# Power_and_CAN_Bus.net
KiCad netlist of a schematic drawn in Altium Designer
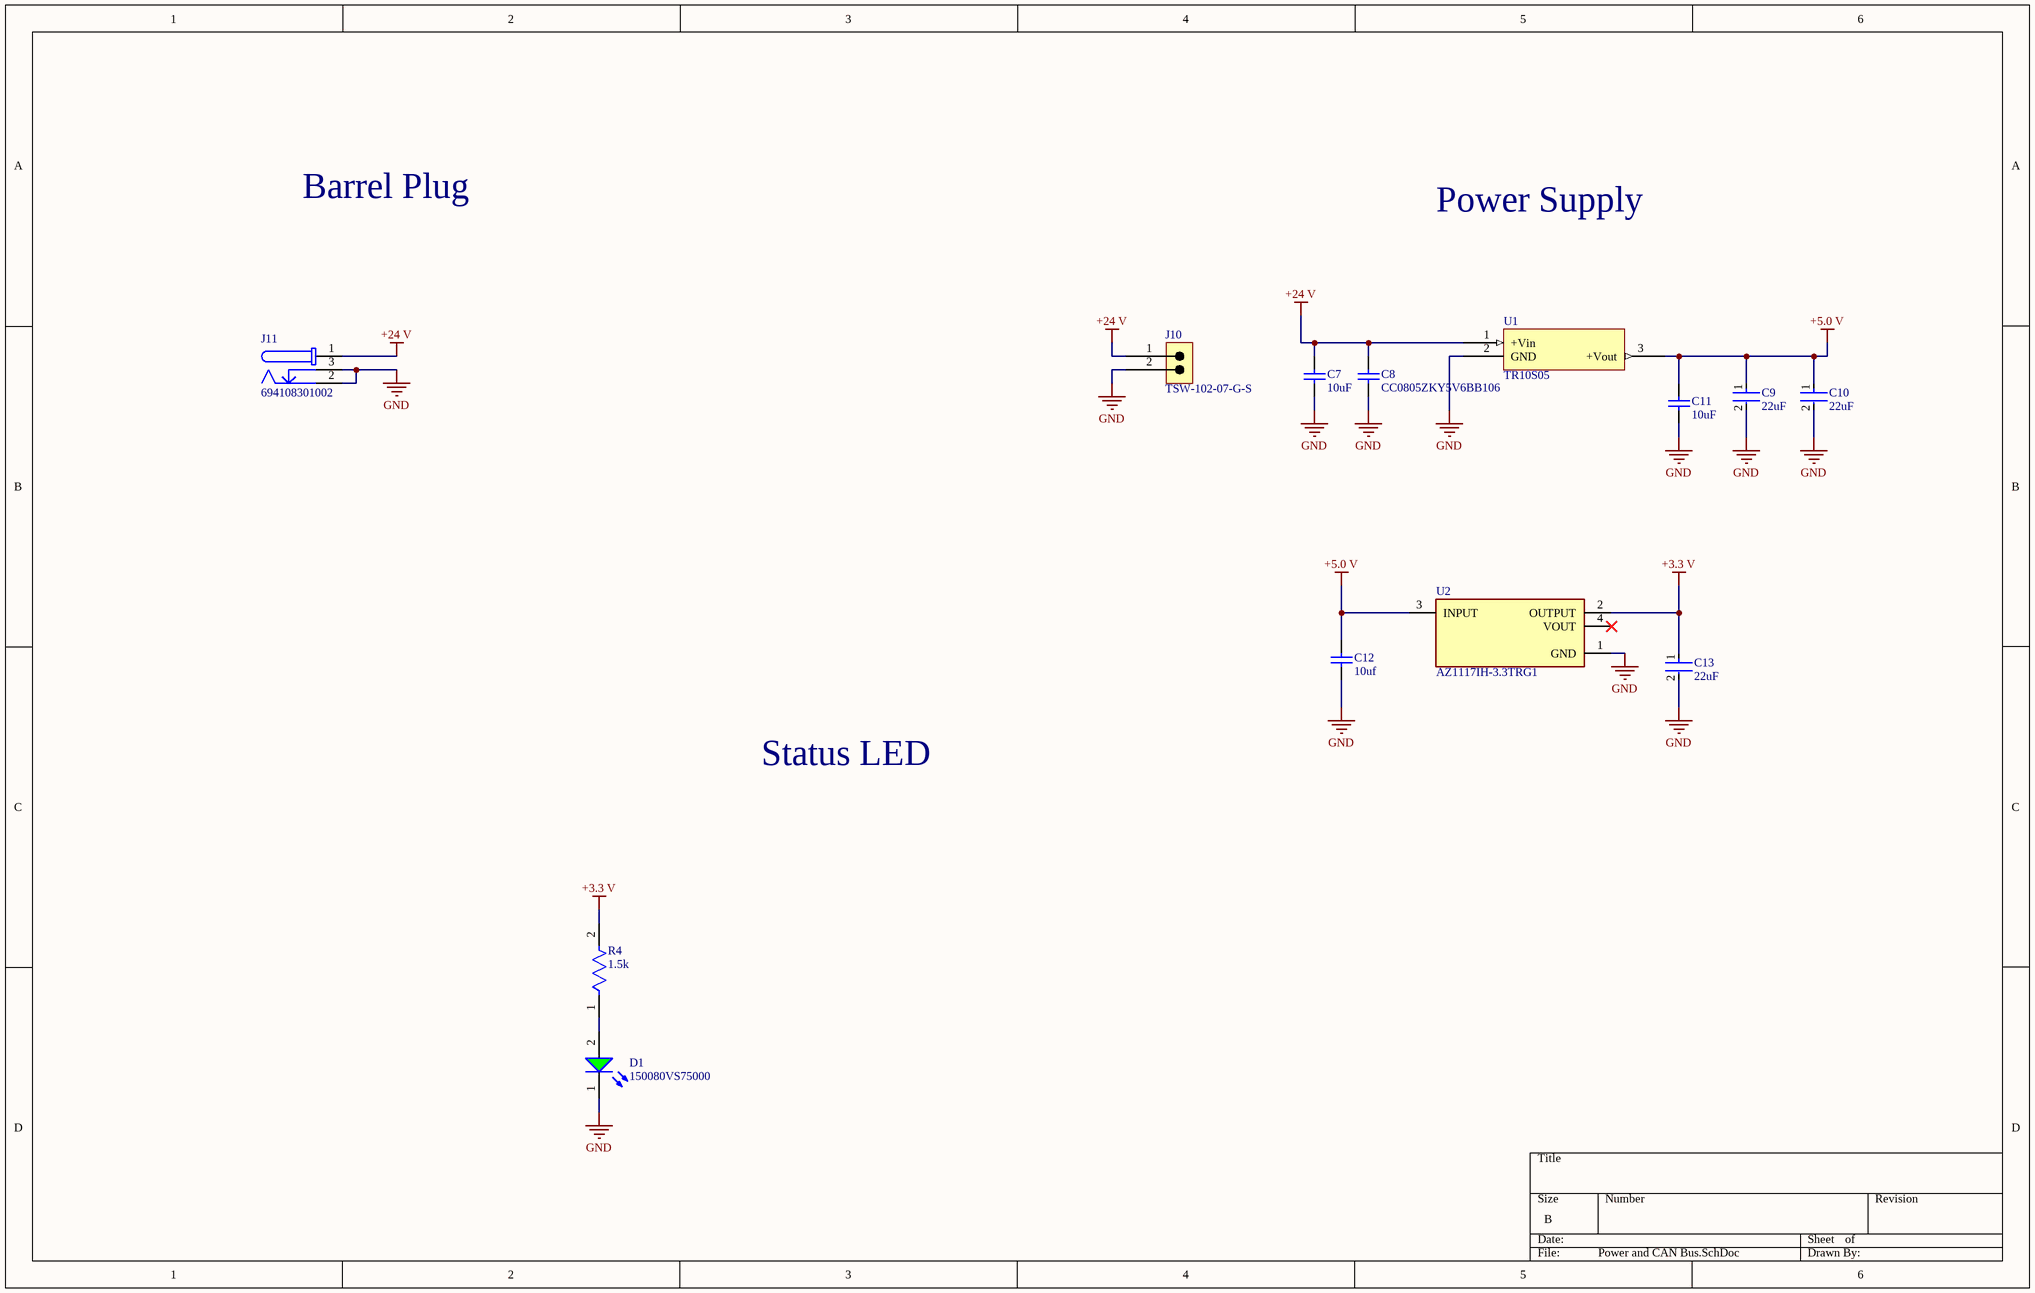
[diagram p0: Power and CAN Bus.SchDoc]

(export (version "E")
  (design (tool "Eeschema 10.0.6"))
  (components
    (comp (ref "C7")
      (value "10uF")
      (footprint "CC0805ZKY5V6BB106-Footprint-1")
      (libsource (lib "C0514760 C0514760") (part "CAP-NP-2"))
    )
    (comp (ref "C8")
      (value "CC0805ZKY5V6BB106")
      (footprint "CC0805ZKY5V6BB106-Footprint-1")
      (libsource (lib "C0514760 C0514760") (part "CAP-NP-2"))
    )
    (comp (ref "C9")
      (value "22uF")
      (footprint "FP-GMC21R-IPC_B")
      (libsource (lib "C0514760 C0514760") (part "b4654b650e69147ec39a6b967a45e02"))
    )
    (comp (ref "C10")
      (value "22uF")
      (footprint "FP-GMC21R-IPC_B")
      (libsource (lib "C0514760 C0514760") (part "b4654b650e69147ec39a6b967a45e02"))
    )
    (comp (ref "C11")
      (value "10uF")
      (footprint "CC0805ZKY5V6BB106-Footprint-1")
      (libsource (lib "C0514760 C0514760") (part "CAP-NP-2"))
    )
    (comp (ref "C12")
      (value "10uf")
      (footprint "CC0805ZKY5V6BB106-Footprint-1")
      (libsource (lib "C0514760 C0514760") (part "CAP-NP-2"))
    )
    (comp (ref "C13")
      (value "22uF")
      (footprint "FP-GMC21R-IPC_B")
      (libsource (lib "C0514760 C0514760") (part "b4654b650e69147ec39a6b967a45e02"))
    )
    (comp (ref "D1")
      (value "150080VS75000")
      (footprint "WL-SMCW_0805_150080xx75000")
      (description "Single Color LED, Bright Green, Water Clear, 1.4mm")
      (libsource (lib "C0514760 C0514760") (part "LED_Green_2A-1K"))
    )
    (comp (ref "J10")
      (value "TSW-102-07-G-S")
      (footprint "FP-TSW-102-07-G-S-MFG")
      (libsource (lib "C0514760 C0514760") (part "3bc925449376181038e59eaffc5286c"))
    )
    (comp (ref "J11")
      (value "694108301002")
      (footprint "694108301002")
      (description "DC Power Jack Connector WR-DC, Male, Right Angled, THT, 5 A, 24 V")
      (libsource (lib "C0514760 C0514760") (part "DC Power Jack"))
    )
    (comp (ref "R4")
      (value "1.5k")
      (footprint "FP-RT0805-IPC_A")
      (description "Fixed Resistor, Thin Film, 0.125W, 1500ohm, 150V, 1% +/-Tol, 50ppm/Cel, Surface Mount, 0805")
      (fields (field (name "POWER") "125mW") (field (name "TOLERANCE") "1%"))
      (libsource (lib "C0514760 C0514760") (part "1029c3af85768c4190bb7ad29bc67b5"))
    )
    (comp (ref "U1")
      (value "TR10S05")
      (footprint "TR10S05-Footprint-1")
      (description "DC-DC Regulated Power Supply Module")
      (libsource (lib "C0514760 C0514760") (part "TR10S05-Symbol-1"))
    )
    (comp (ref "U2")
      (value "AZ1117IH-3.3TRG1")
      (footprint "FP-SOT223-IPC_B")
      (description "Fixed Positive LDO Regulator, 3.3V, 1.3V Dropout, PDSO3")
      (libsource (lib "C0514760 C0514760") (part "3c8a0cc3f7d1fafcf032f21e1bb5f65"))
    )
  )
  (nets
    (net (code "1") (name "+3.3 V") (class "Default")
      (node (ref "C13") (pin "1") (pinfunction "1_1") (pintype "passive"))
      (node (ref "R4") (pin "2") (pinfunction "2_2") (pintype "passive"))
      (node (ref "U2") (pin "2") (pinfunction "OUTPUT_2") (pintype "power_in"))
    )
    (net (code "2") (name "+5.0 V") (class "Default")
      (node (ref "C10") (pin "1") (pinfunction "1_1") (pintype "passive"))
      (node (ref "C11") (pin "2") (pinfunction "2_2") (pintype "passive"))
      (node (ref "C12") (pin "2") (pinfunction "2_2") (pintype "passive"))
      (node (ref "C9") (pin "1") (pinfunction "1_1") (pintype "passive"))
      (node (ref "U1") (pin "3") (pinfunction "+Vout_3") (pintype "output"))
      (node (ref "U2") (pin "3") (pinfunction "INPUT_3") (pintype "power_in"))
    )
    (net (code "3") (name "+24 V") (class "Default")
      (node (ref "C7") (pin "2") (pinfunction "2_2") (pintype "passive"))
      (node (ref "C8") (pin "2") (pinfunction "2_2") (pintype "passive"))
      (node (ref "J10") (pin "1") (pinfunction "1_1") (pintype "passive"))
      (node (ref "J11") (pin "1") (pinfunction "1_1") (pintype "passive"))
      (node (ref "U1") (pin "1") (pinfunction "+Vin_1") (pintype "input"))
    )
    (net (code "4") (name "GND") (class "Default")
      (node (ref "C10") (pin "2") (pinfunction "2_2") (pintype "passive"))
      (node (ref "C11") (pin "1") (pinfunction "1_1") (pintype "passive"))
      (node (ref "C12") (pin "1") (pinfunction "1_1") (pintype "passive"))
      (node (ref "C13") (pin "2") (pinfunction "2_2") (pintype "passive"))
      (node (ref "C7") (pin "1") (pinfunction "1_1") (pintype "passive"))
      (node (ref "C8") (pin "1") (pinfunction "1_1") (pintype "passive"))
      (node (ref "C9") (pin "2") (pinfunction "2_2") (pintype "passive"))
      (node (ref "D1") (pin "1") (pinfunction "K_1") (pintype "passive"))
      (node (ref "J10") (pin "2") (pinfunction "2_2") (pintype "passive"))
      (node (ref "J11") (pin "2") (pinfunction "2_2") (pintype "passive"))
      (node (ref "J11") (pin "3") (pinfunction "3_3") (pintype "passive"))
      (node (ref "U1") (pin "2") (pinfunction "GND_2") (pintype "power_in"))
      (node (ref "U2") (pin "1") (pinfunction "GND_1") (pintype "power_in"))
    )
    (net (code "5") (name "Net-(D1-A)") (class "Default")
      (node (ref "D1") (pin "2") (pinfunction "A_2") (pintype "passive"))
      (node (ref "R4") (pin "1") (pinfunction "1_1") (pintype "passive"))
    )
    (net (code "6") (name "unconnected-(U2-VOUT-Pad4)") (class "Default")
      (node (ref "U2") (pin "4") (pinfunction "VOUT_4") (pintype "power_in+no_connect"))
    )
  )
)
